# FMCPower.net
KiCad netlist of a schematic drawn in Altium Designer
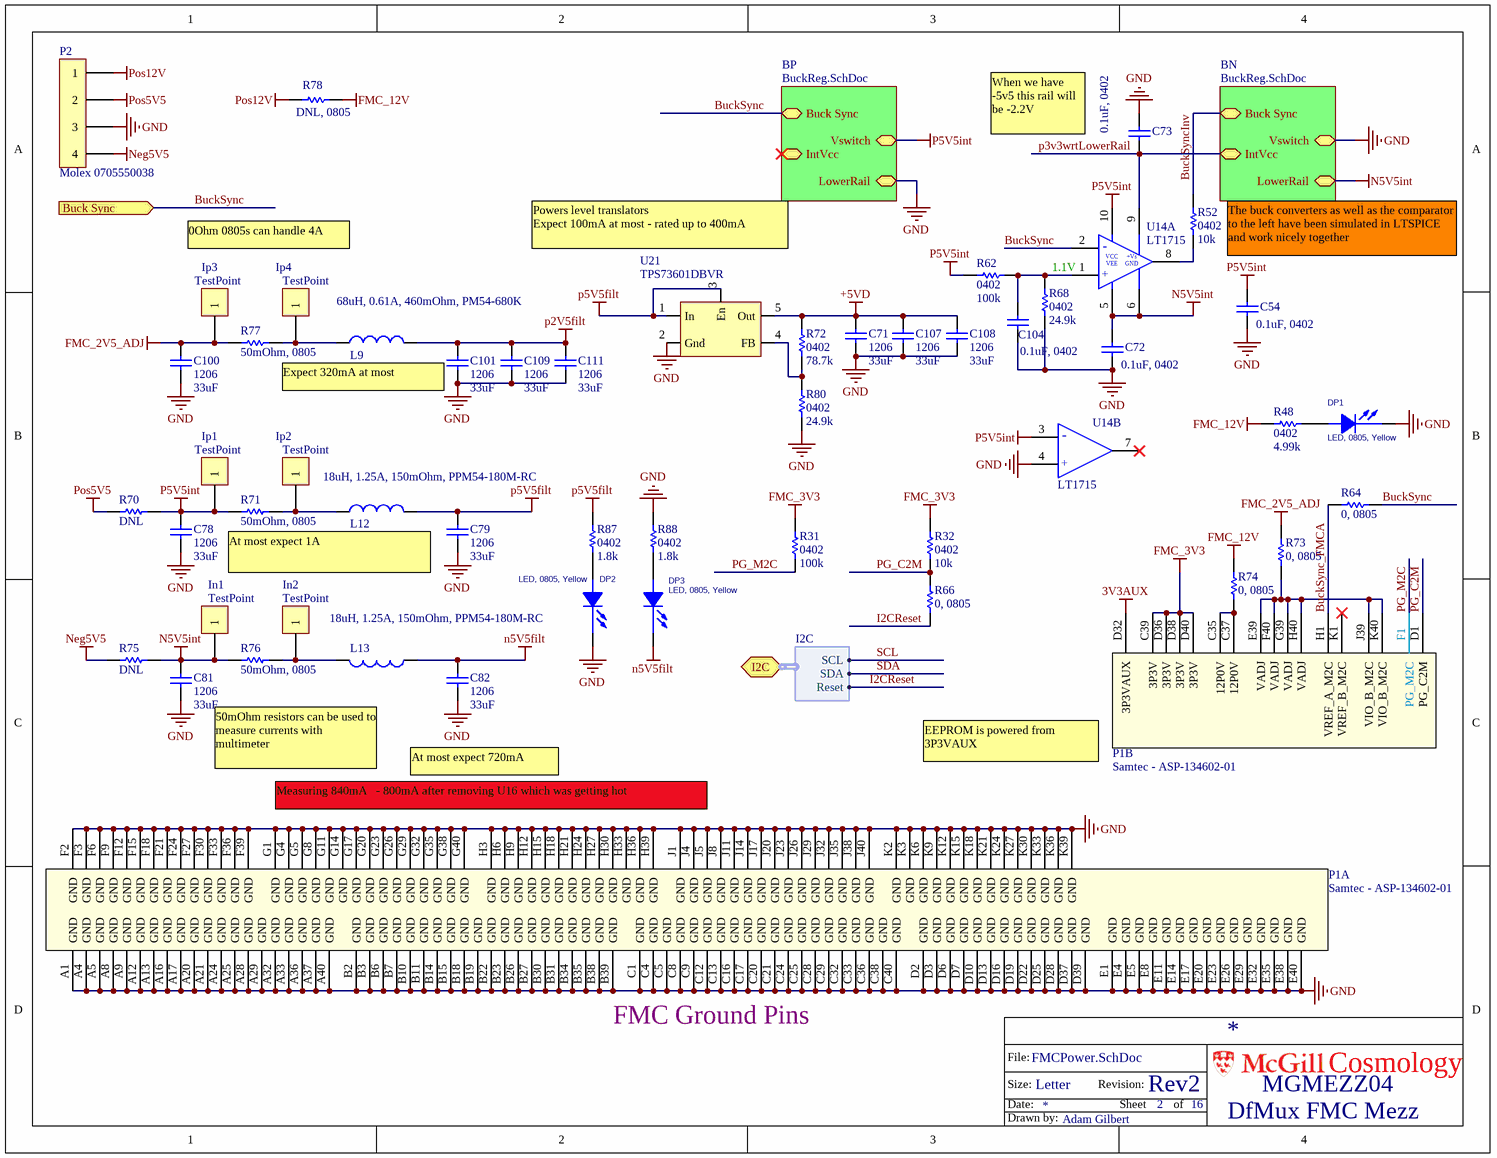
[diagram p0: FMCPower.SchDoc]

(export (version "E")
  (design (tool "Eeschema 10.0.6"))
  (components
    (comp (ref "C54")
      (value "0.1uF, 0402")
      (footprint "0402")
      (description "Capacitor, Ceramic, 0402")
      (fields (field (name "MANUFACTURER") "TDK Corporation"))
      (libsource (lib "MGMEZZ04") (part "CAP 0603"))
    )
    (comp (ref "C71")
      (value "33uF")
      (footprint "1206")
      (description "Capacitor, Ceramic, 1210")
      (fields (field (name "MANUFACTURER") "TDK Corporation"))
      (libsource (lib "MGMEZZ04") (part "CAP 1210"))
    )
    (comp (ref "C72")
      (value "0.1uF, 0402")
      (footprint "0402")
      (description "Capacitor, Ceramic, 0402")
      (fields (field (name "MANUFACTURER") "TDK Corporation"))
      (libsource (lib "MGMEZZ04") (part "CAP 0603"))
    )
    (comp (ref "C73")
      (value "0.1uF, 0402")
      (footprint "0402")
      (description "Capacitor, Ceramic, 0402")
      (fields (field (name "MANUFACTURER") "TDK Corporation"))
      (libsource (lib "MGMEZZ04") (part "CAP 0603"))
    )
    (comp (ref "C78")
      (value "33uF")
      (footprint "1206")
      (description "Capacitor, Ceramic, 1210")
      (fields (field (name "MANUFACTURER") "TDK Corporation"))
      (libsource (lib "MGMEZZ04") (part "CAP 1210"))
    )
    (comp (ref "C79")
      (value "33uF")
      (footprint "1206")
      (description "Capacitor, Ceramic, 1210")
      (fields (field (name "MANUFACTURER") "TDK Corporation"))
      (libsource (lib "MGMEZZ04") (part "CAP 1210"))
    )
    (comp (ref "C81")
      (value "33uF")
      (footprint "1206")
      (description "Capacitor, Ceramic, 1210")
      (fields (field (name "MANUFACTURER") "TDK Corporation"))
      (libsource (lib "MGMEZZ04") (part "CAP 1210"))
    )
    (comp (ref "C82")
      (value "33uF")
      (footprint "1206")
      (description "Capacitor, Ceramic, 1210")
      (fields (field (name "MANUFACTURER") "TDK Corporation"))
      (libsource (lib "MGMEZZ04") (part "CAP 1210"))
    )
    (comp (ref "C100")
      (value "33uF")
      (footprint "1206")
      (description "Capacitor, Ceramic, 1210")
      (fields (field (name "MANUFACTURER") "TDK Corporation"))
      (libsource (lib "MGMEZZ04") (part "CAP 1210"))
    )
    (comp (ref "C101")
      (value "33uF")
      (footprint "1206")
      (description "Capacitor, Ceramic, 1210")
      (fields (field (name "MANUFACTURER") "TDK Corporation"))
      (libsource (lib "MGMEZZ04") (part "CAP 1210"))
    )
    (comp (ref "C104")
      (value "0.1uF, 0402")
      (footprint "0402")
      (description "Capacitor, Ceramic, 0402")
      (fields (field (name "MANUFACTURER") "TDK Corporation"))
      (libsource (lib "MGMEZZ04") (part "CAP 0603"))
    )
    (comp (ref "C107")
      (value "33uF")
      (footprint "1206")
      (description "Capacitor, Ceramic, 1210")
      (fields (field (name "MANUFACTURER") "TDK Corporation"))
      (libsource (lib "MGMEZZ04") (part "CAP 1210"))
    )
    (comp (ref "C108")
      (value "33uF")
      (footprint "1206")
      (description "Capacitor, Ceramic, 1210")
      (fields (field (name "MANUFACTURER") "TDK Corporation"))
      (libsource (lib "MGMEZZ04") (part "CAP 1210"))
    )
    (comp (ref "C109")
      (value "33uF")
      (footprint "1206")
      (description "Capacitor, Ceramic, 1210")
      (fields (field (name "MANUFACTURER") "TDK Corporation"))
      (libsource (lib "MGMEZZ04") (part "CAP 1210"))
    )
    (comp (ref "C111")
      (value "33uF")
      (footprint "1206")
      (description "Capacitor, Ceramic, 1210")
      (fields (field (name "MANUFACTURER") "TDK Corporation"))
      (libsource (lib "MGMEZZ04") (part "CAP 1210"))
    )
    (comp (ref "DP1")
      (value "LED, 0805, Yellow")
      (description "LED")
      (fields (field (name "MANUFACTURER") "Rohm Semiconductor"))
      (libsource (lib "MGMEZZ04") (part "LED, yellow, 0805, 2mA"))
    )
    (comp (ref "DP2")
      (value "LED, 0805, Yellow")
      (description "LED")
      (fields (field (name "MANUFACTURER") "Rohm Semiconductor"))
      (libsource (lib "MGMEZZ04") (part "LED, yellow, 0805, 2mA"))
    )
    (comp (ref "DP3")
      (value "LED, 0805, Yellow")
      (description "LED")
      (fields (field (name "MANUFACTURER") "Rohm Semiconductor"))
      (libsource (lib "MGMEZZ04") (part "LED, yellow, 0805, 2mA"))
    )
    (comp (ref "In1")
      (value "TestPoint")
      (footprint "TP-3520-SK")
      (description "TestPoint1")
      (libsource (lib "MGMEZZ04") (part "TestPoint"))
    )
    (comp (ref "In2")
      (value "TestPoint")
      (footprint "TP-3520-SK")
      (description "TestPoint1")
      (libsource (lib "MGMEZZ04") (part "TestPoint"))
    )
    (comp (ref "Ip1")
      (value "TestPoint")
      (footprint "TP-3520-SK")
      (description "TestPoint1")
      (libsource (lib "MGMEZZ04") (part "TestPoint"))
    )
    (comp (ref "Ip2")
      (value "TestPoint")
      (footprint "TP-3520-SK")
      (description "TestPoint1")
      (libsource (lib "MGMEZZ04") (part "TestPoint"))
    )
    (comp (ref "Ip3")
      (value "TestPoint")
      (footprint "TP-3520-SK")
      (description "TestPoint1")
      (libsource (lib "MGMEZZ04") (part "TestPoint"))
    )
    (comp (ref "Ip4")
      (value "TestPoint")
      (footprint "TP-3520-SK")
      (description "TestPoint1")
      (libsource (lib "MGMEZZ04") (part "TestPoint"))
    )
    (comp (ref "L9")
      (value "68uH")
      (footprint "CHOKEPM54")
      (description "Inductor PM54")
      (fields
        (field (name "MANUFACTURER") "Bourns Inc.")
        (field (name "PART CONSTRAINTS") "68uH, 0.61A, 460mOhm, PM54-680K")
      )
      (libsource (lib "MGMEZZ04") (part "INDPM54"))
    )
    (comp (ref "L12")
      (value "18uH")
      (footprint "CHOKEPM54")
      (description "INDUCTOR UNSHIELD 18UH 1.25A SMD")
      (fields
        (field (name "PART CONSTRAINTS") "18uH, 1.25A, 150mOhm, PPM54-180M-RC")
        (field (name "MANUFACTURER") "Bourns Inc.")
      )
      (libsource (lib "MGMEZZ04") (part "INDPM54"))
    )
    (comp (ref "L13")
      (value "18uH")
      (footprint "CHOKEPM54")
      (description "INDUCTOR UNSHIELD 18UH 1.25A SMD")
      (fields
        (field (name "PART CONSTRAINTS") "18uH, 1.25A, 150mOhm, PPM54-180M-RC")
        (field (name "MANUFACTURER") "Bourns Inc.")
      )
      (libsource (lib "MGMEZZ04") (part "INDPM54"))
    )
    (comp (ref "P1")
      (value "Samtec - ASP-134602-01")
      (footprint "BTB-SM1-27-2V400M")
      (description "Samtec ASP-134602-01")
      (fields (field (name "MANUFACTURER") "Samtec"))
      (libsource (lib "MGMEZZ04") (part "Samtec - ASP-134602-01"))
    )
    (comp (ref "P2")
      (value "Molex 0705550038")
      (footprint "Molex0705550038")
      (description "Molex 4pin header - 0705550038")
      (fields (field (name "MANUFACTURER") "Molex"))
      (libsource (lib "MGMEZZ04") (part "Molex 4pin header - 0705550038"))
    )
    (comp (ref "R31")
      (value "100k")
      (footprint "0402")
      (description "Resistor")
      (fields (field (name "MANUFACTURER") "Generic"))
      (libsource (lib "MGMEZZ04") (part "RES 0402"))
    )
    (comp (ref "R32")
      (value "10k")
      (footprint "0402")
      (description "Resistor")
      (fields (field (name "MANUFACTURER") "Generic"))
      (libsource (lib "MGMEZZ04") (part "RES 0402"))
    )
    (comp (ref "R48")
      (value "4.99k")
      (footprint "0402")
      (description "Resistor")
      (fields (field (name "MANUFACTURER") "Generic"))
      (libsource (lib "MGMEZZ04") (part "RES 0402"))
    )
    (comp (ref "R52")
      (value "10k")
      (footprint "0402")
      (description "Resistor")
      (fields (field (name "MANUFACTURER") "Generic"))
      (libsource (lib "MGMEZZ04") (part "RES 0402"))
    )
    (comp (ref "R62")
      (value "100k")
      (footprint "0402")
      (description "Resistor")
      (fields (field (name "MANUFACTURER") "Generic"))
      (libsource (lib "MGMEZZ04") (part "RES 0402"))
    )
    (comp (ref "R64")
      (value "0, 0805")
      (footprint "0805")
      (description "RES 0.0 OHM 1/8W 0805 SMD")
      (fields (field (name "MANUFACTURER") "e.g Vishay/Dale"))
      (libsource (lib "AdamsParts") (part "Res1812"))
    )
    (comp (ref "R66")
      (value "0, 0805")
      (footprint "0805")
      (description "RES 0.0 OHM 1/8W 0805 SMD")
      (fields (field (name "MANUFACTURER") "e.g Vishay/Dale"))
      (libsource (lib "AdamsParts") (part "Res1812"))
    )
    (comp (ref "R68")
      (value "24.9k")
      (footprint "0402")
      (description "Resistor")
      (fields (field (name "MANUFACTURER") "Generic"))
      (libsource (lib "MGMEZZ04") (part "RES 0402"))
    )
    (comp (ref "R70")
      (value "DNL")
      (footprint "0805")
      (description "RES 0.0 OHM 1/8W 0805 SMD")
      (fields (field (name "MANUFACTURER") "e.g Vishay/Dale"))
      (libsource (lib "AdamsParts") (part "Res1812"))
    )
    (comp (ref "R71")
      (value "50mOhm, 0805")
      (footprint "0805")
      (description "RES 50mOHM 1/4W 0805 SMD")
      (fields (field (name "MANUFACTURER") "Panasonic Electronic Components"))
      (libsource (lib "MGMEZZ04") (part "RES 0805"))
    )
    (comp (ref "R72")
      (value "78.7k")
      (footprint "0402")
      (description "Resistor")
      (fields (field (name "MANUFACTURER") "Generic"))
      (libsource (lib "MGMEZZ04") (part "RES 0402"))
    )
    (comp (ref "R73")
      (value "0, 0805")
      (footprint "0805")
      (description "RES 0.0 OHM 1/8W 0805 SMD")
      (fields (field (name "MANUFACTURER") "e.g Vishay/Dale"))
      (libsource (lib "AdamsParts") (part "Res1812"))
    )
    (comp (ref "R74")
      (value "0, 0805")
      (footprint "0805")
      (description "RES 0.0 OHM 1/8W 0805 SMD")
      (fields (field (name "MANUFACTURER") "e.g Vishay/Dale"))
      (libsource (lib "AdamsParts") (part "Res1812"))
    )
    (comp (ref "R75")
      (value "DNL")
      (footprint "0805")
      (description "RES 0.0 OHM 1/8W 0805 SMD")
      (fields (field (name "MANUFACTURER") "e.g Vishay/Dale"))
      (libsource (lib "AdamsParts") (part "Res1812"))
    )
    (comp (ref "R76")
      (value "50mOhm, 0805")
      (footprint "0805")
      (description "RES 50mOHM 1/4W 0805 SMD")
      (fields (field (name "MANUFACTURER") "Panasonic Electronic Components"))
      (libsource (lib "MGMEZZ04") (part "RES 0805"))
    )
    (comp (ref "R77")
      (value "50mOhm, 0805")
      (footprint "0805")
      (description "RES 50mOHM 1/4W 0805 SMD")
      (fields (field (name "MANUFACTURER") "Panasonic Electronic Components"))
      (libsource (lib "MGMEZZ04") (part "RES 0805"))
    )
    (comp (ref "R78")
      (value "DNL, 0805")
      (footprint "0805")
      (description "RES 0.0 OHM 1/8W 0805 SMD")
      (fields (field (name "MANUFACTURER") "Generic"))
      (libsource (lib "MGMEZZ04") (part "RES 0805"))
    )
    (comp (ref "R80")
      (value "24.9k")
      (footprint "0402")
      (description "Resistor")
      (fields (field (name "MANUFACTURER") "Generic"))
      (libsource (lib "MGMEZZ04") (part "RES 0402"))
    )
    (comp (ref "R87")
      (value "1.8k")
      (footprint "0402")
      (description "Resistor")
      (fields (field (name "MANUFACTURER") "Generic"))
      (libsource (lib "MGMEZZ04") (part "RES 0402"))
    )
    (comp (ref "R88")
      (value "1.8k")
      (footprint "0402")
      (description "Resistor")
      (fields (field (name "MANUFACTURER") "Generic"))
      (libsource (lib "MGMEZZ04") (part "RES 0402"))
    )
    (comp (ref "U14")
      (value "LT1715")
      (footprint "TSSOP50P490X110-10N")
      (description "IC COMPARATOR 150MHZ DUAL 10MSOP")
      (fields (field (name "MANUFACTURER") "Linear Technology"))
      (libsource (lib "MGMEZZ04") (part "LT1715"))
    )
    (comp (ref "U21")
      (value "TPS73601DBVR")
      (footprint "SOT23-5")
      (description "Adjustable 30uVrms noise 400mA regulator")
      (fields (field (name "MANUFACTURER") "Texas Instruments"))
      (libsource (lib "MGMEZZ04") (part "TPS73601DBVR"))
    )
  )
  (nets
    (net (code "2") (name "+5VD") (class "Default")
      (node (ref "C107") (pin "1") (pinfunction "1_1") (pintype "passive"))
      (node (ref "C108") (pin "1") (pinfunction "1_1") (pintype "passive"))
      (node (ref "C71") (pin "1") (pinfunction "1_1") (pintype "passive"))
      (node (ref "R72") (pin "2") (pinfunction "2_2") (pintype "passive"))
      (node (ref "U21") (pin "5") (pinfunction "Out_5") (pintype "passive"))
    )
    (net (code "3") (name "/BuckSync") (class "Default")
      (node (ref "R64") (pin "1") (pinfunction "1_1") (pintype "passive"))
      (node (ref "U14") (pin "2") (pinfunction "-_2") (pintype "power_in"))
    )
    (net (code "4") (name "/BuckSyncInv") (class "Default")
      (node (ref "R52") (pin "1") (pinfunction "1_1") (pintype "passive"))
    )
    (net (code "5") (name "/BuckSync_FMCA") (class "Default")
      (node (ref "P1") (pin "H1") (pinfunction "VREF_A_M2C_H1") (pintype "passive"))
      (node (ref "R64") (pin "2") (pinfunction "2_2") (pintype "passive"))
    )
    (net (code "6") (name "/I2CReset") (class "Default")
      (node (ref "R66") (pin "2") (pinfunction "2_2") (pintype "passive"))
    )
    (net (code "8") (name "/PG_C2M") (class "Default")
      (node (ref "P1") (pin "D1") (pinfunction "PG_C2M_D1") (pintype "passive"))
      (node (ref "R32") (pin "2") (pinfunction "2_2") (pintype "passive"))
      (node (ref "R66") (pin "1") (pinfunction "1_1") (pintype "passive"))
    )
    (net (code "9") (name "/PG_M2C") (class "Default")
      (node (ref "P1") (pin "F1") (pinfunction "PG_M2C_F1") (pintype "passive"))
      (node (ref "R31") (pin "2") (pinfunction "2_2") (pintype "passive"))
    )
    (net (code "12") (name "/p3v3wrtLowerRail") (class "Default")
      (node (ref "C73") (pin "1") (pinfunction "1_1") (pintype "passive"))
      (node (ref "U14") (pin "9") (pinfunction "Vs_9") (pintype "power_in"))
    )
    (net (code "14") (name "3V3AUX") (class "Default")
      (node (ref "P1") (pin "D32") (pinfunction "3P3VAUX_D32") (pintype "passive"))
    )
    (net (code "15") (name "FMC_2V5_ADJ") (class "Default")
      (node (ref "C100") (pin "1") (pinfunction "1_1") (pintype "passive"))
      (node (ref "Ip3") (pin "1") (pinfunction "1_1") (pintype "passive"))
      (node (ref "R73") (pin "2") (pinfunction "2_2") (pintype "passive"))
      (node (ref "R77") (pin "1") (pinfunction "1_1") (pintype "passive"))
    )
    (net (code "16") (name "FMC_3V3") (class "Default")
      (node (ref "P1") (pin "C39") (pinfunction "3P3V_C39") (pintype "passive"))
      (node (ref "P1") (pin "D36") (pinfunction "3P3V_D36") (pintype "passive"))
      (node (ref "P1") (pin "D38") (pinfunction "3P3V_D38") (pintype "passive"))
      (node (ref "P1") (pin "D40") (pinfunction "3P3V_D40") (pintype "passive"))
      (node (ref "R31") (pin "1") (pinfunction "1_1") (pintype "passive"))
      (node (ref "R32") (pin "1") (pinfunction "1_1") (pintype "passive"))
    )
    (net (code "17") (name "FMC_12V") (class "Default")
      (node (ref "R48") (pin "1") (pinfunction "1_1") (pintype "passive"))
      (node (ref "R74") (pin "2") (pinfunction "2_2") (pintype "passive"))
      (node (ref "R78") (pin "2") (pinfunction "2_2") (pintype "passive"))
    )
    (net (code "18") (name "GND") (class "Default")
      (node (ref "C100") (pin "2") (pinfunction "2_2") (pintype "passive"))
      (node (ref "C101") (pin "2") (pinfunction "2_2") (pintype "passive"))
      (node (ref "C104") (pin "1") (pinfunction "1_1") (pintype "passive"))
      (node (ref "C107") (pin "2") (pinfunction "2_2") (pintype "passive"))
      (node (ref "C108") (pin "2") (pinfunction "2_2") (pintype "passive"))
      (node (ref "C109") (pin "2") (pinfunction "2_2") (pintype "passive"))
      (node (ref "C111") (pin "2") (pinfunction "2_2") (pintype "passive"))
      (node (ref "C54") (pin "1") (pinfunction "1_1") (pintype "passive"))
      (node (ref "C71") (pin "2") (pinfunction "2_2") (pintype "passive"))
      (node (ref "C72") (pin "1") (pinfunction "1_1") (pintype "passive"))
      (node (ref "C73") (pin "2") (pinfunction "2_2") (pintype "passive"))
      (node (ref "C78") (pin "2") (pinfunction "2_2") (pintype "passive"))
      (node (ref "C79") (pin "2") (pinfunction "2_2") (pintype "passive"))
      (node (ref "C81") (pin "2") (pinfunction "2_2") (pintype "passive"))
      (node (ref "C82") (pin "2") (pinfunction "2_2") (pintype "passive"))
      (node (ref "DP1") (pin "2") (pinfunction "CATHODE_2") (pintype "passive"))
      (node (ref "DP2") (pin "2") (pinfunction "CATHODE_2") (pintype "passive"))
      (node (ref "P1") (pin "A1") (pinfunction "GND_A1") (pintype "passive"))
      (node (ref "P1") (pin "A12") (pinfunction "GND_A12") (pintype "passive"))
      (node (ref "P1") (pin "A13") (pinfunction "GND_A13") (pintype "passive"))
      (node (ref "P1") (pin "A16") (pinfunction "GND_A16") (pintype "passive"))
      (node (ref "P1") (pin "A17") (pinfunction "GND_A17") (pintype "passive"))
      (node (ref "P1") (pin "A20") (pinfunction "GND_A20") (pintype "passive"))
      (node (ref "P1") (pin "A21") (pinfunction "GND_A21") (pintype "passive"))
      (node (ref "P1") (pin "A24") (pinfunction "GND_A24") (pintype "passive"))
      (node (ref "P1") (pin "A25") (pinfunction "GND_A25") (pintype "passive"))
      (node (ref "P1") (pin "A28") (pinfunction "GND_A28") (pintype "passive"))
      (node (ref "P1") (pin "A29") (pinfunction "GND_A29") (pintype "passive"))
      (node (ref "P1") (pin "A32") (pinfunction "GND_A32") (pintype "passive"))
      (node (ref "P1") (pin "A33") (pinfunction "GND_A33") (pintype "passive"))
      (node (ref "P1") (pin "A36") (pinfunction "GND_A36") (pintype "passive"))
      (node (ref "P1") (pin "A37") (pinfunction "GND_A37") (pintype "passive"))
      (node (ref "P1") (pin "A4") (pinfunction "GND_A4") (pintype "passive"))
      (node (ref "P1") (pin "A40") (pinfunction "GND_A40") (pintype "passive"))
      (node (ref "P1") (pin "A5") (pinfunction "GND_A5") (pintype "passive"))
      (node (ref "P1") (pin "A8") (pinfunction "GND_A8") (pintype "passive"))
      (node (ref "P1") (pin "A9") (pinfunction "GND_A9") (pintype "passive"))
      (node (ref "P1") (pin "B10") (pinfunction "GND_B10") (pintype "passive"))
      (node (ref "P1") (pin "B11") (pinfunction "GND_B11") (pintype "passive"))
      (node (ref "P1") (pin "B14") (pinfunction "GND_B14") (pintype "passive"))
      (node (ref "P1") (pin "B15") (pinfunction "GND_B15") (pintype "passive"))
      (node (ref "P1") (pin "B18") (pinfunction "GND_B18") (pintype "passive"))
      (node (ref "P1") (pin "B19") (pinfunction "GND_B19") (pintype "passive"))
      (node (ref "P1") (pin "B2") (pinfunction "GND_B2") (pintype "passive"))
      (node (ref "P1") (pin "B22") (pinfunction "GND_B22") (pintype "passive"))
      (node (ref "P1") (pin "B23") (pinfunction "GND_B23") (pintype "passive"))
      (node (ref "P1") (pin "B26") (pinfunction "GND_B26") (pintype "passive"))
      (node (ref "P1") (pin "B27") (pinfunction "GND_B27") (pintype "passive"))
      (node (ref "P1") (pin "B3") (pinfunction "GND_B3") (pintype "passive"))
      (node (ref "P1") (pin "B30") (pinfunction "GND_B30") (pintype "passive"))
      (node (ref "P1") (pin "B31") (pinfunction "GND_B31") (pintype "passive"))
      (node (ref "P1") (pin "B34") (pinfunction "GND_B34") (pintype "passive"))
      (node (ref "P1") (pin "B35") (pinfunction "GND_B35") (pintype "passive"))
      (node (ref "P1") (pin "B38") (pinfunction "GND_B38") (pintype "passive"))
      (node (ref "P1") (pin "B39") (pinfunction "GND_B39") (pintype "passive"))
      (node (ref "P1") (pin "B6") (pinfunction "GND_B6") (pintype "passive"))
      (node (ref "P1") (pin "B7") (pinfunction "GND_B7") (pintype "passive"))
      (node (ref "P1") (pin "C1") (pinfunction "GND_C1") (pintype "passive"))
      (node (ref "P1") (pin "C12") (pinfunction "GND_C12") (pintype "passive"))
      (node (ref "P1") (pin "C13") (pinfunction "GND_C13") (pintype "passive"))
      (node (ref "P1") (pin "C16") (pinfunction "GND_C16") (pintype "passive"))
      (node (ref "P1") (pin "C17") (pinfunction "GND_C17") (pintype "passive"))
      (node (ref "P1") (pin "C20") (pinfunction "GND_C20") (pintype "passive"))
      (node (ref "P1") (pin "C21") (pinfunction "GND_C21") (pintype "passive"))
      (node (ref "P1") (pin "C24") (pinfunction "GND_C24") (pintype "passive"))
      (node (ref "P1") (pin "C25") (pinfunction "GND_C25") (pintype "passive"))
      (node (ref "P1") (pin "C28") (pinfunction "GND_C28") (pintype "passive"))
      (node (ref "P1") (pin "C29") (pinfunction "GND_C29") (pintype "passive"))
      (node (ref "P1") (pin "C32") (pinfunction "GND_C32") (pintype "passive"))
      (node (ref "P1") (pin "C33") (pinfunction "GND_C33") (pintype "passive"))
      (node (ref "P1") (pin "C36") (pinfunction "GND_C36") (pintype "passive"))
      (node (ref "P1") (pin "C38") (pinfunction "GND_C38") (pintype "passive"))
      (node (ref "P1") (pin "C4") (pinfunction "GND_C4") (pintype "passive"))
      (node (ref "P1") (pin "C40") (pinfunction "GND_C40") (pintype "passive"))
      (node (ref "P1") (pin "C5") (pinfunction "GND_C5") (pintype "passive"))
      (node (ref "P1") (pin "C8") (pinfunction "GND_C8") (pintype "passive"))
      (node (ref "P1") (pin "C9") (pinfunction "GND_C9") (pintype "passive"))
      (node (ref "P1") (pin "D10") (pinfunction "GND_D10") (pintype "passive"))
      (node (ref "P1") (pin "D13") (pinfunction "GND_D13") (pintype "passive"))
      (node (ref "P1") (pin "D16") (pinfunction "GND_D16") (pintype "passive"))
      (node (ref "P1") (pin "D19") (pinfunction "GND_D19") (pintype "passive"))
      (node (ref "P1") (pin "D2") (pinfunction "GND_D2") (pintype "passive"))
      (node (ref "P1") (pin "D22") (pinfunction "GND_D22") (pintype "passive"))
      (node (ref "P1") (pin "D25") (pinfunction "GND_D25") (pintype "passive"))
      (node (ref "P1") (pin "D28") (pinfunction "GND_D28") (pintype "passive"))
      (node (ref "P1") (pin "D3") (pinfunction "GND_D3") (pintype "passive"))
      (node (ref "P1") (pin "D37") (pinfunction "GND_D37") (pintype "passive"))
      (node (ref "P1") (pin "D39") (pinfunction "GND_D39") (pintype "passive"))
      (node (ref "P1") (pin "D6") (pinfunction "GND_D6") (pintype "passive"))
      (node (ref "P1") (pin "D7") (pinfunction "GND_D7") (pintype "passive"))
      (node (ref "P1") (pin "E1") (pinfunction "GND_E1") (pintype "passive"))
      (node (ref "P1") (pin "E11") (pinfunction "GND_E11") (pintype "passive"))
      (node (ref "P1") (pin "E14") (pinfunction "GND_E14") (pintype "passive"))
      (node (ref "P1") (pin "E17") (pinfunction "GND_E17") (pintype "passive"))
      (node (ref "P1") (pin "E20") (pinfunction "GND_E20") (pintype "passive"))
      (node (ref "P1") (pin "E23") (pinfunction "GND_E23") (pintype "passive"))
      (node (ref "P1") (pin "E26") (pinfunction "GND_E26") (pintype "passive"))
      (node (ref "P1") (pin "E29") (pinfunction "GND_E29") (pintype "passive"))
      (node (ref "P1") (pin "E32") (pinfunction "GND_E32") (pintype "passive"))
      (node (ref "P1") (pin "E35") (pinfunction "GND_E35") (pintype "passive"))
      (node (ref "P1") (pin "E38") (pinfunction "GND_E38") (pintype "passive"))
      (node (ref "P1") (pin "E4") (pinfunction "GND_E4") (pintype "passive"))
      (node (ref "P1") (pin "E40") (pinfunction "GND_E40") (pintype "passive"))
      (node (ref "P1") (pin "E5") (pinfunction "GND_E5") (pintype "passive"))
      (node (ref "P1") (pin "E8") (pinfunction "GND_E8") (pintype "passive"))
      (node (ref "P1") (pin "F12") (pinfunction "GND_F12") (pintype "passive"))
      (node (ref "P1") (pin "F15") (pinfunction "GND_F15") (pintype "passive"))
      (node (ref "P1") (pin "F18") (pinfunction "GND_F18") (pintype "passive"))
      (node (ref "P1") (pin "F2") (pinfunction "GND_F2") (pintype "passive"))
      (node (ref "P1") (pin "F21") (pinfunction "GND_F21") (pintype "passive"))
      (node (ref "P1") (pin "F24") (pinfunction "GND_F24") (pintype "passive"))
      (node (ref "P1") (pin "F27") (pinfunction "GND_F27") (pintype "passive"))
      (node (ref "P1") (pin "F3") (pinfunction "GND_F3") (pintype "passive"))
      (node (ref "P1") (pin "F30") (pinfunction "GND_F30") (pintype "passive"))
      (node (ref "P1") (pin "F33") (pinfunction "GND_F33") (pintype "passive"))
      (node (ref "P1") (pin "F36") (pinfunction "GND_F36") (pintype "passive"))
      (node (ref "P1") (pin "F39") (pinfunction "GND_F39") (pintype "passive"))
      (node (ref "P1") (pin "F6") (pinfunction "GND_F6") (pintype "passive"))
      (node (ref "P1") (pin "F9") (pinfunction "GND_F9") (pintype "passive"))
      (node (ref "P1") (pin "G1") (pinfunction "GND_G1") (pintype "passive"))
      (node (ref "P1") (pin "G11") (pinfunction "GND_G11") (pintype "passive"))
      (node (ref "P1") (pin "G14") (pinfunction "GND_G14") (pintype "passive"))
      (node (ref "P1") (pin "G17") (pinfunction "GND_G17") (pintype "passive"))
      (node (ref "P1") (pin "G20") (pinfunction "GND_G20") (pintype "passive"))
      (node (ref "P1") (pin "G23") (pinfunction "GND_G23") (pintype "passive"))
      (node (ref "P1") (pin "G26") (pinfunction "GND_G26") (pintype "passive"))
      (node (ref "P1") (pin "G29") (pinfunction "GND_G29") (pintype "passive"))
      (node (ref "P1") (pin "G32") (pinfunction "GND_G32") (pintype "passive"))
      (node (ref "P1") (pin "G35") (pinfunction "GND_G35") (pintype "passive"))
      (node (ref "P1") (pin "G38") (pinfunction "GND_G38") (pintype "passive"))
      (node (ref "P1") (pin "G4") (pinfunction "GND_G4") (pintype "passive"))
      (node (ref "P1") (pin "G40") (pinfunction "GND_G40") (pintype "passive"))
      (node (ref "P1") (pin "G5") (pinfunction "GND_G5") (pintype "passive"))
      (node (ref "P1") (pin "G8") (pinfunction "GND_G8") (pintype "passive"))
      (node (ref "P1") (pin "H12") (pinfunction "GND_H12") (pintype "passive"))
      (node (ref "P1") (pin "H15") (pinfunction "GND_H15") (pintype "passive"))
      (node (ref "P1") (pin "H18") (pinfunction "GND_H18") (pintype "passive"))
      (node (ref "P1") (pin "H21") (pinfunction "GND_H21") (pintype "passive"))
      (node (ref "P1") (pin "H24") (pinfunction "GND_H24") (pintype "passive"))
      (node (ref "P1") (pin "H27") (pinfunction "GND_H27") (pintype "passive"))
      (node (ref "P1") (pin "H3") (pinfunction "GND_H3") (pintype "passive"))
      (node (ref "P1") (pin "H30") (pinfunction "GND_H30") (pintype "passive"))
      (node (ref "P1") (pin "H33") (pinfunction "GND_H33") (pintype "passive"))
      (node (ref "P1") (pin "H36") (pinfunction "GND_H36") (pintype "passive"))
      (node (ref "P1") (pin "H39") (pinfunction "GND_H39") (pintype "passive"))
      (node (ref "P1") (pin "H6") (pinfunction "GND_H6") (pintype "passive"))
      (node (ref "P1") (pin "H9") (pinfunction "GND_H9") (pintype "passive"))
      (node (ref "P1") (pin "J1") (pinfunction "GND_J1") (pintype "passive"))
      (node (ref "P1") (pin "J11") (pinfunction "GND_J11") (pintype "passive"))
      (node (ref "P1") (pin "J14") (pinfunction "GND_J14") (pintype "passive"))
      (node (ref "P1") (pin "J17") (pinfunction "GND_J17") (pintype "passive"))
      (node (ref "P1") (pin "J20") (pinfunction "GND_J20") (pintype "passive"))
      (node (ref "P1") (pin "J23") (pinfunction "GND_J23") (pintype "passive"))
      (node (ref "P1") (pin "J26") (pinfunction "GND_J26") (pintype "passive"))
      (node (ref "P1") (pin "J29") (pinfunction "GND_J29") (pintype "passive"))
      (node (ref "P1") (pin "J32") (pinfunction "GND_J32") (pintype "passive"))
      (node (ref "P1") (pin "J35") (pinfunction "GND_J35") (pintype "passive"))
      (node (ref "P1") (pin "J38") (pinfunction "GND_J38") (pintype "passive"))
      (node (ref "P1") (pin "J4") (pinfunction "GND_J4") (pintype "passive"))
      (node (ref "P1") (pin "J40") (pinfunction "GND_J40") (pintype "passive"))
      (node (ref "P1") (pin "J5") (pinfunction "GND_J5") (pintype "passive"))
      (node (ref "P1") (pin "J8") (pinfunction "GND_J8") (pintype "passive"))
      (node (ref "P1") (pin "K12") (pinfunction "GND_K12") (pintype "passive"))
      (node (ref "P1") (pin "K15") (pinfunction "GND_K15") (pintype "passive"))
      (node (ref "P1") (pin "K18") (pinfunction "GND_K18") (pintype "passive"))
      (node (ref "P1") (pin "K2") (pinfunction "GND_K2") (pintype "passive"))
      (node (ref "P1") (pin "K21") (pinfunction "GND_K21") (pintype "passive"))
      (node (ref "P1") (pin "K24") (pinfunction "GND_K24") (pintype "passive"))
      (node (ref "P1") (pin "K27") (pinfunction "GND_K27") (pintype "passive"))
      (node (ref "P1") (pin "K3") (pinfunction "GND_K3") (pintype "passive"))
      (node (ref "P1") (pin "K30") (pinfunction "GND_K30") (pintype "passive"))
      (node (ref "P1") (pin "K33") (pinfunction "GND_K33") (pintype "passive"))
      (node (ref "P1") (pin "K36") (pinfunction "GND_K36") (pintype "passive"))
      (node (ref "P1") (pin "K39") (pinfunction "GND_K39") (pintype "passive"))
      (node (ref "P1") (pin "K6") (pinfunction "GND_K6") (pintype "passive"))
      (node (ref "P1") (pin "K9") (pinfunction "GND_K9") (pintype "passive"))
      (node (ref "P2") (pin "3") (pinfunction "3_3") (pintype "passive"))
      (node (ref "R68") (pin "2") (pinfunction "2_2") (pintype "passive"))
      (node (ref "R80") (pin "1") (pinfunction "1_1") (pintype "passive"))
      (node (ref "R88") (pin "1") (pinfunction "1_1") (pintype "passive"))
      (node (ref "U14") (pin "4") (pinfunction "+_4") (pintype "passive"))
      (node (ref "U21") (pin "2") (pinfunction "Gnd_2") (pintype "passive"))
    )
    (net (code "19") (name "N5V5int") (class "Default")
      (node (ref "C72") (pin "2") (pinfunction "2_2") (pintype "passive"))
      (node (ref "C81") (pin "1") (pinfunction "1_1") (pintype "passive"))
      (node (ref "In1") (pin "1") (pinfunction "1_1") (pintype "passive"))
      (node (ref "R75") (pin "1") (pinfunction "1_1") (pintype "passive"))
      (node (ref "R76") (pin "1") (pinfunction "1_1") (pintype "passive"))
      (node (ref "U14") (pin "5") (pinfunction "Vee_5") (pintype "power_in"))
      (node (ref "U14") (pin "6") (pinfunction "Gnd_6") (pintype "power_in"))
    )
    (net (code "20") (name "Neg5V5") (class "Default")
      (node (ref "P2") (pin "4") (pinfunction "4_4") (pintype "passive"))
      (node (ref "R75") (pin "2") (pinfunction "2_2") (pintype "passive"))
    )
    (net (code "21") (name "Net-(DP1-ANODE)") (class "Default")
      (node (ref "DP1") (pin "1") (pinfunction "ANODE_1") (pintype "passive"))
      (node (ref "R48") (pin "2") (pinfunction "2_2") (pintype "passive"))
    )
    (net (code "22") (name "Net-(DP2-ANODE)") (class "Default")
      (node (ref "DP2") (pin "1") (pinfunction "ANODE_1") (pintype "passive"))
      (node (ref "R87") (pin "2") (pinfunction "2_2") (pintype "passive"))
    )
    (net (code "23") (name "Net-(DP3-ANODE)") (class "Default")
      (node (ref "DP3") (pin "1") (pinfunction "ANODE_1") (pintype "passive"))
      (node (ref "R88") (pin "2") (pinfunction "2_2") (pintype "passive"))
    )
    (net (code "24") (name "Net-(In2-Pad1)") (class "Default")
      (node (ref "In2") (pin "1") (pinfunction "1_1") (pintype "passive"))
      (node (ref "L13") (pin "2") (pinfunction "2_2") (pintype "passive"))
      (node (ref "R76") (pin "2") (pinfunction "2_2") (pintype "passive"))
    )
    (net (code "25") (name "Net-(Ip2-Pad1)") (class "Default")
      (node (ref "Ip2") (pin "1") (pinfunction "1_1") (pintype "passive"))
      (node (ref "L12") (pin "1") (pinfunction "1_1") (pintype "passive"))
      (node (ref "R71") (pin "2") (pinfunction "2_2") (pintype "passive"))
    )
    (net (code "26") (name "Net-(Ip4-Pad1)") (class "Default")
      (node (ref "Ip4") (pin "1") (pinfunction "1_1") (pintype "passive"))
      (node (ref "L9") (pin "1") (pinfunction "1_1") (pintype "passive"))
      (node (ref "R77") (pin "2") (pinfunction "2_2") (pintype "passive"))
    )
    (net (code "27") (name "Net-(P1B-12P0V-PadC35)") (class "Default")
      (node (ref "P1") (pin "C35") (pinfunction "12P0V_C35") (pintype "passive"))
      (node (ref "P1") (pin "C37") (pinfunction "12P0V_C37") (pintype "passive"))
      (node (ref "R74") (pin "1") (pinfunction "1_1") (pintype "passive"))
    )
    (net (code "28") (name "Net-(P1B-VADJ-PadE39)") (class "Default")
      (node (ref "P1") (pin "E39") (pinfunction "VADJ_E39") (pintype "passive"))
      (node (ref "P1") (pin "F40") (pinfunction "VADJ_F40") (pintype "passive"))
      (node (ref "P1") (pin "G39") (pinfunction "VADJ_G39") (pintype "passive"))
      (node (ref "P1") (pin "H40") (pinfunction "VADJ_H40") (pintype "passive"))
      (node (ref "P1") (pin "J39") (pinfunction "VIO_B_M2C_J39") (pintype "passive"))
      (node (ref "P1") (pin "K40") (pinfunction "VIO_B_M2C_K40") (pintype "passive"))
      (node (ref "R73") (pin "1") (pinfunction "1_1") (pintype "passive"))
    )
    (net (code "29") (name "Net-(U14A-+)") (class "Default")
      (node (ref "C104") (pin "2") (pinfunction "2_2") (pintype "passive"))
      (node (ref "R62") (pin "2") (pinfunction "2_2") (pintype "passive"))
      (node (ref "R68") (pin "1") (pinfunction "1_1") (pintype "passive"))
      (node (ref "U14") (pin "1") (pinfunction "+_1") (pintype "passive"))
    )
    (net (code "30") (name "Net-(U14A-Out)") (class "Default")
      (node (ref "R52") (pin "2") (pinfunction "2_2") (pintype "passive"))
      (node (ref "U14") (pin "8") (pinfunction "Out_8") (pintype "passive"))
    )
    (net (code "31") (name "Net-(U21-FB)") (class "Default")
      (node (ref "R72") (pin "1") (pinfunction "1_1") (pintype "passive"))
      (node (ref "R80") (pin "2") (pinfunction "2_2") (pintype "passive"))
      (node (ref "U21") (pin "4") (pinfunction "FB_4") (pintype "passive"))
    )
    (net (code "32") (name "P5V5int") (class "Default")
      (node (ref "C54") (pin "2") (pinfunction "2_2") (pintype "passive"))
      (node (ref "C78") (pin "1") (pinfunction "1_1") (pintype "passive"))
      (node (ref "Ip1") (pin "1") (pinfunction "1_1") (pintype "passive"))
      (node (ref "R62") (pin "1") (pinfunction "1_1") (pintype "passive"))
      (node (ref "R70") (pin "1") (pinfunction "1_1") (pintype "passive"))
      (node (ref "R71") (pin "1") (pinfunction "1_1") (pintype "passive"))
      (node (ref "U14") (pin "10") (pinfunction "Vcc_10") (pintype "power_in"))
      (node (ref "U14") (pin "3") (pinfunction "-_3") (pintype "power_in"))
    )
    (net (code "33") (name "Pos5V5") (class "Default")
      (node (ref "P2") (pin "2") (pinfunction "2_2") (pintype "passive"))
      (node (ref "R70") (pin "2") (pinfunction "2_2") (pintype "passive"))
    )
    (net (code "34") (name "Pos12V") (class "Default")
      (node (ref "P2") (pin "1") (pinfunction "1_1") (pintype "passive"))
      (node (ref "R78") (pin "1") (pinfunction "1_1") (pintype "passive"))
    )
    (net (code "35") (name "n5V5filt") (class "Default")
      (node (ref "C82") (pin "1") (pinfunction "1_1") (pintype "passive"))
      (node (ref "DP3") (pin "2") (pinfunction "CATHODE_2") (pintype "passive"))
      (node (ref "L13") (pin "1") (pinfunction "1_1") (pintype "passive"))
    )
    (net (code "36") (name "p2V5filt") (class "Default")
      (node (ref "C101") (pin "1") (pinfunction "1_1") (pintype "passive"))
      (node (ref "C109") (pin "1") (pinfunction "1_1") (pintype "passive"))
      (node (ref "C111") (pin "1") (pinfunction "1_1") (pintype "passive"))
      (node (ref "L9") (pin "2") (pinfunction "2_2") (pintype "passive"))
    )
    (net (code "37") (name "p5V5filt") (class "Default")
      (node (ref "C79") (pin "1") (pinfunction "1_1") (pintype "passive"))
      (node (ref "L12") (pin "2") (pinfunction "2_2") (pintype "passive"))
      (node (ref "R87") (pin "1") (pinfunction "1_1") (pintype "passive"))
      (node (ref "U21") (pin "1") (pinfunction "In_1") (pintype "passive"))
      (node (ref "U21") (pin "3") (pinfunction "En_3") (pintype "passive"))
    )
    (net (code "38") (name "unconnected-(P1B-VREF_B_M2C-PadK1)") (class "Default")
      (node (ref "P1") (pin "K1") (pinfunction "VREF_B_M2C_K1") (pintype "passive+no_connect"))
    )
    (net (code "39") (name "unconnected-(U14B-Out-Pad7)") (class "Default")
      (node (ref "U14") (pin "7") (pinfunction "Out_7") (pintype "passive+no_connect"))
    )
  )
)
